# HIVE_SIGHT_USB.net
KiCad netlist of a schematic drawn in Altium Designer
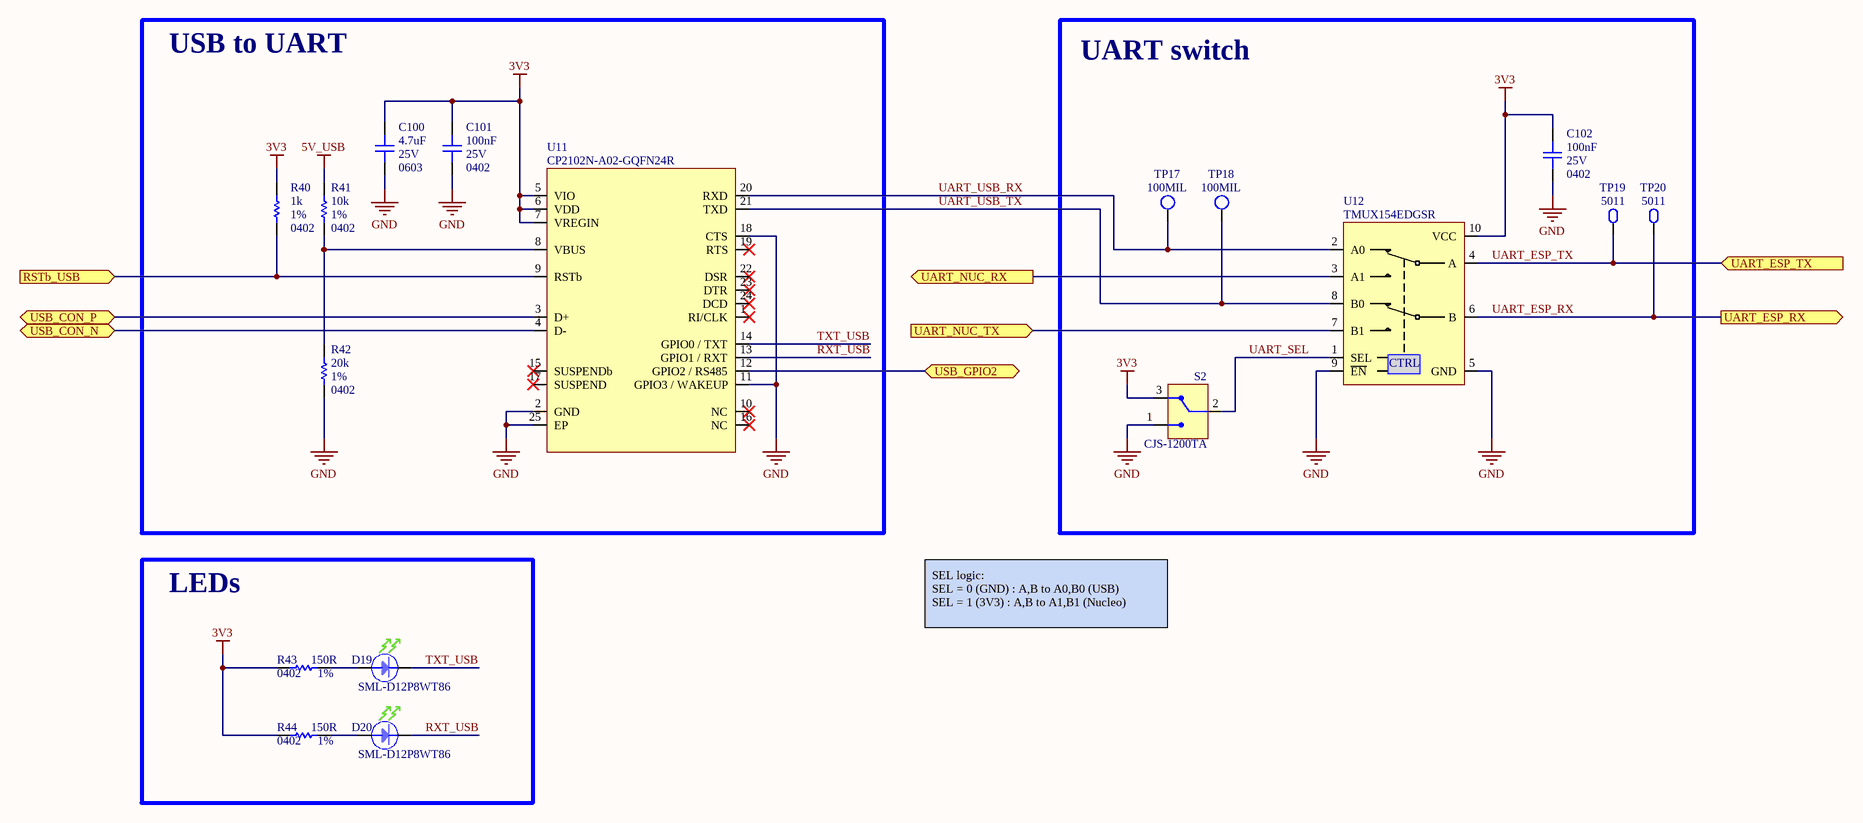
[diagram p0: HIVE_SIGHT_USB.SchDoc]

(export (version "E")
  (design (tool "Eeschema 10.0.6"))
  (components
    (comp (ref "C100")
      (value "4.7uF")
      (footprint "CAP_CER_0603")
      (description "CAP - CER 4.7µF 20% 25V X5R - 0603")
      (fields
        (field (name "TOLERANCE") "20%")
        (field (name "PACKAGE") "0603")
        (field (name "VOLTAGE RATING") "25V")
        (field (name "Comment") "CL10A475MA8NQNC")
        (field (name "CREATEDBY/DATE") "Nicolas Roy 2018-11-21")
        (field (name "VERIFIEDBY") "Nicolas V. (2019-01-22)")
      )
      (libsource (lib "GRAMS_MASTER_LIB") (part "CAP_CER_CL10A475MA8NQNC"))
    )
    (comp (ref "C101")
      (value "100nF")
      (footprint "GRAMS_MASTER_LIB_PCB:CAP_CER_0402")
      (description "CAP - CER 0.1µF 10% 25V X7R - 0402")
      (fields
        (field (name "TOLERANCE") "10%")
        (field (name "PACKAGE") "0402")
        (field (name "VOLTAGE RATING") "25V")
        (field (name "Comment") "CGA2B3X7R1E104K050BB")
        (field (name "CREATEDBY/DATE") "Nicolas Roy 2018-11-07")
        (field (name "VERIFIEDBY") "Nicolas V. (2019-01-22)")
      )
      (libsource (lib "GRAMS_MASTER_LIB_SCH") (part "CAP_CER_CGA2B3X7R1E104K050BB"))
    )
    (comp (ref "C102")
      (value "100nF")
      (footprint "GRAMS_MASTER_LIB_PCB:CAP_CER_0402")
      (description "CAP - CER 0.1µF 10% 25V X7R - 0402")
      (fields
        (field (name "TOLERANCE") "10%")
        (field (name "PACKAGE") "0402")
        (field (name "VOLTAGE RATING") "25V")
        (field (name "Comment") "CGA2B3X7R1E104K050BB")
        (field (name "CREATEDBY/DATE") "Nicolas Roy 2018-11-07")
        (field (name "VERIFIEDBY") "Nicolas V. (2019-01-22)")
      )
      (libsource (lib "GRAMS_MASTER_LIB_SCH") (part "CAP_CER_CGA2B3X7R1E104K050BB"))
    )
    (comp (ref "D19")
      (value "SML-D12P8WT86")
      (footprint "GRAMS_MASTER_LIB_PCB:LED_SML-D12P8WT86")
      (description "LED - GREEN DIFFUSED 0603 SMD - 0603")
      (fields
        (field (name "CREATEDBY/DATE") "Keven Deslandes - 2018/11/21")
        (field (name "VERIFIEDBY") "Caroline Paulin - 13 février 2019")
      )
      (libsource (lib "GRAMS_MASTER_LIB_SCH") (part "LED_SML-D12P8WT86"))
    )
    (comp (ref "D20")
      (value "SML-D12P8WT86")
      (footprint "GRAMS_MASTER_LIB_PCB:LED_SML-D12P8WT86")
      (description "LED - GREEN DIFFUSED 0603 SMD - 0603")
      (fields
        (field (name "CREATEDBY/DATE") "Keven Deslandes - 2018/11/21")
        (field (name "VERIFIEDBY") "Caroline Paulin - 13 février 2019")
      )
      (libsource (lib "GRAMS_MASTER_LIB_SCH") (part "LED_SML-D12P8WT86"))
    )
    (comp (ref "R40")
      (value "1k")
      (footprint "GRAMS_MASTER_LIB_PCB:RES_0402")
      (description "RES - 1K OHM 1% 1/16W - 0402")
      (fields
        (field (name "TOLERANCE") "1%")
        (field (name "PACKAGE") "0402")
        (field (name "Comment") "RC0402FR-071KL")
        (field (name "CREATEDBY/DATE") "Jonathan Bouchard 2018-07-05")
        (field (name "VERIFIEDBY") "Arnaud Samson 16-07-18")
      )
      (libsource (lib "GRAMS_MASTER_LIB_SCH") (part "RES_RC0402FR-071KL"))
    )
    (comp (ref "R41")
      (value "10k")
      (footprint "GRAMS_MASTER_LIB_PCB:RES_0402")
      (description "RES - 10K OHMS 1% 1/16W - 0402")
      (fields
        (field (name "TOLERANCE") "1%")
        (field (name "PACKAGE") "0402")
        (field (name "Comment") "RC0402FR-0710KL")
        (field (name "CREATEDBY/DATE") "Nicolas V. (2018-11-20)")
        (field (name "VERIFIEDBY") "Nicolas V. (2018-11-20)")
      )
      (libsource (lib "GRAMS_MASTER_LIB_SCH") (part "RES_RC0402FR-0710KL"))
    )
    (comp (ref "R42")
      (value "20k")
      (footprint "GRAMS_MASTER_LIB_PCB:RES_0402")
      (description "RES - 20K 1% 1/16W  - 0402")
      (fields
        (field (name "TOLERANCE") "1%")
        (field (name "PACKAGE") "0402")
        (field (name "Comment") "RC0402FR-0720KL")
        (field (name "CREATEDBY/DATE") "Keven Deslandes 2018-10-18")
        (field (name "VERIFIEDBY") "Caroline Paulin - 7 janv 2019")
      )
      (libsource (lib "GRAMS_MASTER_LIB_SCH") (part "RES_RC0402FR-0720KL"))
    )
    (comp (ref "R43")
      (value "150R")
      (footprint "RES_0402")
      (description "RES - 150R 1% 1/16W - 0402")
      (fields
        (field (name "TOLERANCE") "1%")
        (field (name "PACKAGE") "0402")
        (field (name "Comment") "RC0402FR-07150RL")
        (field (name "CREATEDBY/DATE") "Jonathan Bouchard 2019-03-25")
        (field (name "VERIFIEDBY") "Nicolas V. (2019-05-02)")
      )
      (libsource (lib "GRAMS_MASTER_LIB") (part "RES_RC0402FR-07150RL"))
    )
    (comp (ref "R44")
      (value "150R")
      (footprint "RES_0402")
      (description "RES - 150R 1% 1/16W - 0402")
      (fields
        (field (name "TOLERANCE") "1%")
        (field (name "PACKAGE") "0402")
        (field (name "Comment") "RC0402FR-07150RL")
        (field (name "CREATEDBY/DATE") "Jonathan Bouchard 2019-03-25")
        (field (name "VERIFIEDBY") "Nicolas V. (2019-05-02)")
      )
      (libsource (lib "GRAMS_MASTER_LIB") (part "RES_RC0402FR-07150RL"))
    )
    (comp (ref "S2")
      (value "CJS-1200TA")
      (footprint "SWI_SPDT_CJS-1200TA")
      (description "SWI - SLIDE SPDT 100MA 6V - SMD")
      (fields
        (field (name "CREATEDBY/DATE") "Caroline Paulin - 15/11/2018")
        (field (name "VERIFIEDBY") "Nicolas V. (2018-11-16)")
      )
      (libsource (lib "GRAMS_MASTER_LIB") (part "SWI_SPDT_CJS-1200TA"))
    )
    (comp (ref "TP17")
      (value "100MIL")
      (footprint "grams_master_lib_pcb:TPO_TH_ROUND_100MIL")
      (description "TPO - TEST POINT ROUND TH  - 100MIL")
      (fields
        (field (name "CREATEDBY/DATE") "Louis-Daniel Gaulin/ 14/01/2020")
        (field (name "VERIFIEDBY") "C.Paulin - 21/01/2020")
      )
      (libsource (lib "GRAMS_MASTER_LIB_SCH") (part "TPO_TH_ROUND_100MIL"))
    )
    (comp (ref "TP18")
      (value "100MIL")
      (footprint "grams_master_lib_pcb:TPO_TH_ROUND_100MIL")
      (description "TPO - TEST POINT ROUND TH  - 100MIL")
      (fields
        (field (name "CREATEDBY/DATE") "Louis-Daniel Gaulin/ 14/01/2020")
        (field (name "VERIFIEDBY") "C.Paulin - 21/01/2020")
      )
      (libsource (lib "GRAMS_MASTER_LIB_SCH") (part "TPO_TH_ROUND_100MIL"))
    )
    (comp (ref "TP19")
      (value "5011")
      (footprint "TPO_5011")
      (description "TPO - TEST POINT - TH")
      (fields
        (field (name "CREATEDBY/DATE") "Louis-Daniel Gauli / 02-11-2020")
        (field (name "VERIFIEDBY") "Philippe Arsenault/2020-11-06")
      )
      (libsource (lib "SWARMUS_LIB") (part "TPO_5011"))
    )
    (comp (ref "TP20")
      (value "5011")
      (footprint "TPO_5011")
      (description "TPO - TEST POINT - TH")
      (fields
        (field (name "CREATEDBY/DATE") "Louis-Daniel Gauli / 02-11-2020")
        (field (name "VERIFIEDBY") "Philippe Arsenault/2020-11-06")
      )
      (libsource (lib "SWARMUS_LIB") (part "TPO_5011"))
    )
    (comp (ref "U11")
      (value "CP2102N-A02-GQFN24R")
      (footprint "COM_XCV_CP2102N-A02-GQFN24R")
      (description "COM_XCV - IC USB TO UART BRIDGE - 24-QFN (4x4)")
      (fields
        (field (name "CREATEDBY/DATE") "Louis-Daniel Gaulin / 06-10-2020")
        (field (name "VERIFIEDBY") "Philippe Arsenault/2020-11-06")
      )
      (libsource (lib "SWARMUS_LIB") (part "COM_XCV_CP2102N-A02-GQFN24R"))
    )
    (comp (ref "U12")
      (value "TMUX154EDGSR")
      (footprint "LOG_MUX_TMUX154EDGSR")
      (description "LOG_MUX -  SWITCH SPDT DUAL 2:1 - 10-VSSOP")
      (fields
        (field (name "CREATEDBY/DATE") "Louis-Daniel Gaulin / 06-10-2020")
        (field (name "VERIFIEDBY") "Philippe Arsenault/2020-11-06")
      )
      (libsource (lib "SWARMUS_LIB") (part "LOG_MUX_TMUX154EDGSR"))
    )
  )
  (nets
    (net (code "1") (name "/RSTb_USB") (class "Default")
      (node (ref "R40") (pin "2") (pinfunction "2_2") (pintype "passive"))
      (node (ref "U11") (pin "9") (pinfunction "RSTb_9") (pintype "passive"))
    )
    (net (code "2") (name "/RXT_USB") (class "Default")
      (node (ref "D20") (pin "K") (pinfunction "K_K") (pintype "passive"))
      (node (ref "U11") (pin "13") (pinfunction "GPIO1_/_RXT_13") (pintype "passive"))
    )
    (net (code "3") (name "/TXT_USB") (class "Default")
      (node (ref "D19") (pin "K") (pinfunction "K_K") (pintype "passive"))
      (node (ref "U11") (pin "14") (pinfunction "GPIO0_/_TXT_14") (pintype "passive"))
    )
    (net (code "4") (name "/UART_ESP_RX") (class "Default")
      (node (ref "TP20") (pin "1") (pinfunction "1_1") (pintype "passive"))
      (node (ref "U12") (pin "6") (pinfunction "B_6") (pintype "passive"))
    )
    (net (code "5") (name "/UART_ESP_TX") (class "Default")
      (node (ref "TP19") (pin "1") (pinfunction "1_1") (pintype "passive"))
      (node (ref "U12") (pin "4") (pinfunction "A_4") (pintype "passive"))
    )
    (net (code "6") (name "/UART_NUC_RX") (class "Default")
      (node (ref "U12") (pin "3") (pinfunction "A1_3") (pintype "passive"))
    )
    (net (code "7") (name "/UART_NUC_TX") (class "Default")
      (node (ref "U12") (pin "7") (pinfunction "B1_7") (pintype "passive"))
    )
    (net (code "8") (name "/UART_SEL") (class "Default")
      (node (ref "S2") (pin "2") (pinfunction "2_2") (pintype "passive"))
      (node (ref "U12") (pin "1") (pinfunction "SEL_1") (pintype "passive"))
    )
    (net (code "9") (name "/UART_USB_RX") (class "Default")
      (node (ref "TP17") (pin "1") (pinfunction "1_1") (pintype "passive"))
      (node (ref "U11") (pin "20") (pinfunction "RXD_20") (pintype "passive"))
      (node (ref "U12") (pin "2") (pinfunction "A0_2") (pintype "passive"))
    )
    (net (code "10") (name "/UART_USB_TX") (class "Default")
      (node (ref "TP18") (pin "1") (pinfunction "1_1") (pintype "passive"))
      (node (ref "U11") (pin "21") (pinfunction "TXD_21") (pintype "passive"))
      (node (ref "U12") (pin "8") (pinfunction "B0_8") (pintype "passive"))
    )
    (net (code "11") (name "/USB_CON_N") (class "Default")
      (node (ref "U11") (pin "4") (pinfunction "D-_4") (pintype "passive"))
    )
    (net (code "12") (name "/USB_CON_P") (class "Default")
      (node (ref "U11") (pin "3") (pinfunction "D+_3") (pintype "passive"))
    )
    (net (code "13") (name "/USB_GPIO2") (class "Default")
      (node (ref "U11") (pin "12") (pinfunction "GPIO2_/_RS485_12") (pintype "passive"))
    )
    (net (code "14") (name "3V3") (class "Default")
      (node (ref "C100") (pin "2") (pinfunction "2_2") (pintype "passive"))
      (node (ref "C101") (pin "2") (pinfunction "2_2") (pintype "passive"))
      (node (ref "C102") (pin "1") (pinfunction "1_1") (pintype "passive"))
      (node (ref "R40") (pin "1") (pinfunction "1_1") (pintype "passive"))
      (node (ref "R43") (pin "1") (pinfunction "1_1") (pintype "passive"))
      (node (ref "R44") (pin "1") (pinfunction "1_1") (pintype "passive"))
      (node (ref "S2") (pin "3") (pinfunction "3_3") (pintype "passive"))
      (node (ref "U11") (pin "5") (pinfunction "VIO_5") (pintype "passive"))
      (node (ref "U11") (pin "6") (pinfunction "VDD_6") (pintype "passive"))
      (node (ref "U11") (pin "7") (pinfunction "VREGIN_7") (pintype "passive"))
      (node (ref "U12") (pin "10") (pinfunction "VCC_10") (pintype "passive"))
    )
    (net (code "15") (name "5V_USB") (class "Default")
      (node (ref "R41") (pin "2") (pinfunction "2_2") (pintype "passive"))
    )
    (net (code "16") (name "GND") (class "Default")
      (node (ref "C100") (pin "1") (pinfunction "1_1") (pintype "passive"))
      (node (ref "C101") (pin "1") (pinfunction "1_1") (pintype "passive"))
      (node (ref "C102") (pin "2") (pinfunction "2_2") (pintype "passive"))
      (node (ref "R42") (pin "1") (pinfunction "1_1") (pintype "passive"))
      (node (ref "S2") (pin "1") (pinfunction "1_1") (pintype "passive"))
      (node (ref "U11") (pin "11") (pinfunction "GPIO3_/_WAKEUP_11") (pintype "passive"))
      (node (ref "U11") (pin "18") (pinfunction "CTS_18") (pintype "passive"))
      (node (ref "U11") (pin "2") (pinfunction "GND_2") (pintype "passive"))
      (node (ref "U11") (pin "25") (pinfunction "EP_25") (pintype "passive"))
      (node (ref "U12") (pin "5") (pinfunction "GND_5") (pintype "passive"))
      (node (ref "U12") (pin "9") (pinfunction "EN_9") (pintype "passive"))
    )
    (net (code "17") (name "Net-(D19-PadA)") (class "Default")
      (node (ref "D19") (pin "A") (pinfunction "A_A") (pintype "passive"))
      (node (ref "R43") (pin "2") (pinfunction "2_2") (pintype "passive"))
    )
    (net (code "18") (name "Net-(D20-PadA)") (class "Default")
      (node (ref "D20") (pin "A") (pinfunction "A_A") (pintype "passive"))
      (node (ref "R44") (pin "2") (pinfunction "2_2") (pintype "passive"))
    )
    (net (code "19") (name "Net-(U11-VBUS)") (class "Default")
      (node (ref "R41") (pin "1") (pinfunction "1_1") (pintype "passive"))
      (node (ref "R42") (pin "2") (pinfunction "2_2") (pintype "passive"))
      (node (ref "U11") (pin "8") (pinfunction "VBUS_8") (pintype "passive"))
    )
    (net (code "20") (name "unconnected-(U11-DCD-Pad24)") (class "Default")
      (node (ref "U11") (pin "24") (pinfunction "DCD_24") (pintype "passive+no_connect"))
    )
    (net (code "21") (name "unconnected-(U11-DSR-Pad22)") (class "Default")
      (node (ref "U11") (pin "22") (pinfunction "DSR_22") (pintype "passive+no_connect"))
    )
    (net (code "22") (name "unconnected-(U11-DTR-Pad23)") (class "Default")
      (node (ref "U11") (pin "23") (pinfunction "DTR_23") (pintype "passive+no_connect"))
    )
    (net (code "23") (name "unconnected-(U11-NC-Pad10)") (class "Default")
      (node (ref "U11") (pin "10") (pinfunction "NC_10") (pintype "passive+no_connect"))
    )
    (net (code "24") (name "unconnected-(U11-NC-Pad16)") (class "Default")
      (node (ref "U11") (pin "16") (pinfunction "NC_16") (pintype "passive+no_connect"))
    )
    (net (code "25") (name "unconnected-(U11-RI{slash}CLK-Pad1)") (class "Default")
      (node (ref "U11") (pin "1") (pinfunction "RI/CLK_1") (pintype "passive+no_connect"))
    )
    (net (code "26") (name "unconnected-(U11-RTS-Pad19)") (class "Default")
      (node (ref "U11") (pin "19") (pinfunction "RTS_19") (pintype "passive+no_connect"))
    )
    (net (code "27") (name "unconnected-(U11-SUSPEND-Pad17)") (class "Default")
      (node (ref "U11") (pin "17") (pinfunction "SUSPEND_17") (pintype "passive+no_connect"))
    )
    (net (code "28") (name "unconnected-(U11-SUSPENDb-Pad15)") (class "Default")
      (node (ref "U11") (pin "15") (pinfunction "SUSPENDb_15") (pintype "passive+no_connect"))
    )
  )
)
